# design.net
KiCad netlist of a schematic drawn in Altium Designer
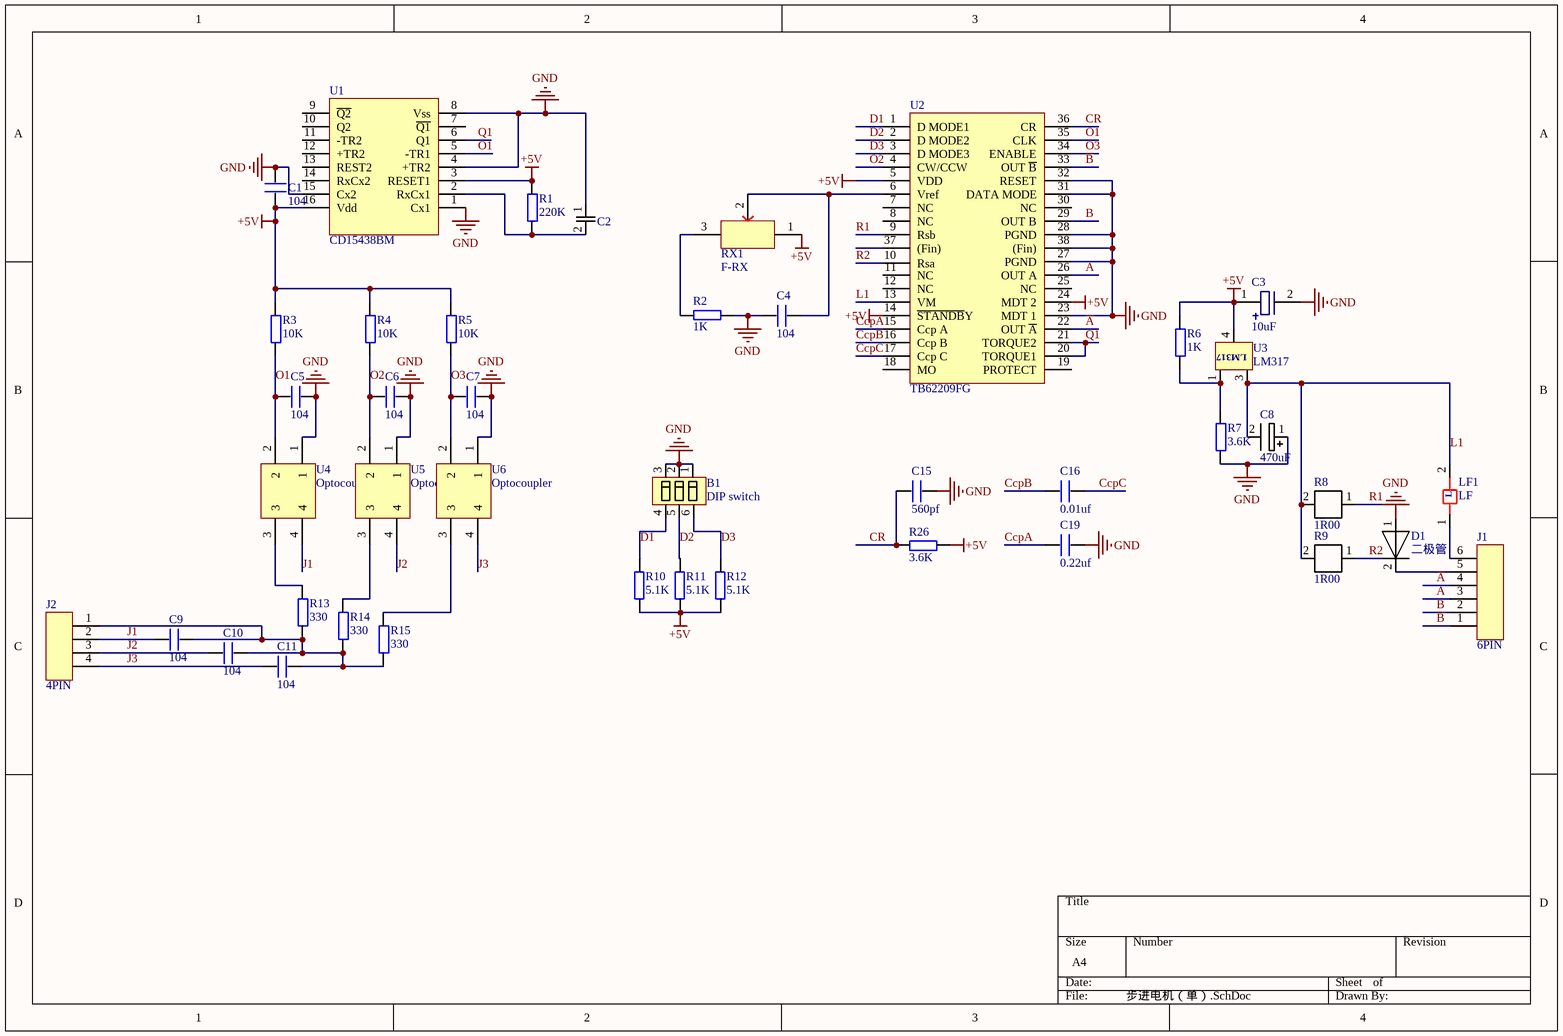
[diagram p0: 步进电机（单）.SchDoc]

(export (version "E")
  (design (tool "Eeschema 10.0.6"))
  (components
    (comp (ref "B1") (value "DIP switch") (libsource (lib "*") (part "拨码开关-3")))
    (comp (ref "C1") (value "104") (footprint "0603P") (libsource (lib "底板封装库") (part "C")))
    (comp (ref "C2") (value "SOP-CAP") (footprint "0805") (libsource (lib "mylib") (part "SOP-CAP")))
    (comp (ref "C3") (value "10uF") (footprint "CAP") (libsource (lib "*") (part "cap10uF")))
    (comp (ref "C4") (value "104") (footprint "0603P") (libsource (lib "底板封装库") (part "C")))
    (comp (ref "C5") (value "104") (footprint "0603P") (libsource (lib "底板封装库") (part "C")))
    (comp (ref "C6") (value "104") (footprint "0603P") (libsource (lib "底板封装库") (part "C")))
    (comp (ref "C7") (value "104") (footprint "0603P") (libsource (lib "底板封装库") (part "C")))
    (comp (ref "C8") (value "470uF") (footprint "470uF CAP") (libsource (lib "*") (part "470uF")))
    (comp (ref "C9") (value "104") (footprint "0603P") (libsource (lib "底板封装库") (part "C")))
    (comp (ref "C10") (value "104") (footprint "0603P") (libsource (lib "底板封装库") (part "C")))
    (comp (ref "C11") (value "104") (footprint "0603P") (libsource (lib "底板封装库") (part "C")))
    (comp (ref "C15") (value "560pf") (footprint "0603P") (libsource (lib "底板封装库") (part "C")))
    (comp (ref "C16") (value "0.01uf") (footprint "0603P") (libsource (lib "底板封装库") (part "C")))
    (comp (ref "C19") (value "0.22uf") (footprint "0603P") (libsource (lib "底板封装库") (part "C")))
    (comp (ref "D1") (value "二极管") (libsource (lib "*") (part "二极管")))
    (comp (ref "J1") (value "6PIN") (footprint "6PIN") (libsource (lib "*") (part "6PIN")))
    (comp (ref "J2") (value "4PIN") (footprint "4PIN") (libsource (lib "*") (part "4PIN")))
    (comp (ref "LF1") (value "LF") (footprint "LF") (libsource (lib "*") (part "LF")))
    (comp (ref "R1")
      (value "220K")
      (footprint "0603P")
      (fields (field (name "Comment") "22R"))
      (libsource (lib "底板封装库") (part "R"))
    )
    (comp (ref "R2")
      (value "1K")
      (footprint "0603P")
      (fields (field (name "Comment") "22R"))
      (libsource (lib "底板封装库") (part "R"))
    )
    (comp (ref "R3")
      (value "10K")
      (footprint "0603P")
      (fields (field (name "Comment") "22R"))
      (libsource (lib "底板封装库") (part "R"))
    )
    (comp (ref "R4")
      (value "10K")
      (footprint "0603P")
      (fields (field (name "Comment") "22R"))
      (libsource (lib "底板封装库") (part "R"))
    )
    (comp (ref "R5")
      (value "10K")
      (footprint "0603P")
      (fields (field (name "Comment") "22R"))
      (libsource (lib "底板封装库") (part "R"))
    )
    (comp (ref "R6")
      (value "1K")
      (footprint "0603P")
      (fields (field (name "Comment") "22R"))
      (libsource (lib "底板封装库") (part "R"))
    )
    (comp (ref "R7")
      (value "3.6K")
      (footprint "0603P")
      (fields (field (name "Comment") "22R"))
      (libsource (lib "底板封装库") (part "R"))
    )
    (comp (ref "R8") (value "1R00") (footprint "1R00") (libsource (lib "mylib") (part "1R00")))
    (comp (ref "R9") (value "1R00") (footprint "1R00") (libsource (lib "mylib") (part "1R00")))
    (comp (ref "R10")
      (value "5.1K")
      (footprint "0603P")
      (fields (field (name "Comment") "22R"))
      (libsource (lib "底板封装库") (part "R"))
    )
    (comp (ref "R11")
      (value "5.1K")
      (footprint "0603P")
      (fields (field (name "Comment") "22R"))
      (libsource (lib "底板封装库") (part "R"))
    )
    (comp (ref "R12")
      (value "5.1K")
      (footprint "0603P")
      (fields (field (name "Comment") "22R"))
      (libsource (lib "底板封装库") (part "R"))
    )
    (comp (ref "R13")
      (value "330")
      (footprint "0603P")
      (fields (field (name "Comment") "22R"))
      (libsource (lib "底板封装库") (part "R"))
    )
    (comp (ref "R14")
      (value "330")
      (footprint "0603P")
      (fields (field (name "Comment") "22R"))
      (libsource (lib "底板封装库") (part "R"))
    )
    (comp (ref "R15")
      (value "330")
      (footprint "0603P")
      (fields (field (name "Comment") "22R"))
      (libsource (lib "底板封装库") (part "R"))
    )
    (comp (ref "R26")
      (value "3.6K")
      (footprint "0603P")
      (fields (field (name "Comment") "22R"))
      (libsource (lib "底板封装库") (part "R"))
    )
    (comp (ref "RX1") (value "F-RX") (footprint "F-RX") (libsource (lib "*") (part "F-RX")))
    (comp (ref "U1") (value "CD15438BM") (footprint "CD14538BM") (libsource (lib "mylib") (part "CD15438BM")))
    (comp (ref "U2") (value "TB62209FG") (footprint "TB62209FG") (libsource (lib "*") (part "TB62209FG")))
    (comp (ref "U3") (value "LM317") (footprint "LM317-SOP") (libsource (lib "*") (part "LM317")))
    (comp (ref "U4") (value "Optocoupler") (libsource (lib "*") (part "光耦")))
    (comp (ref "U5") (value "Optocoupler") (libsource (lib "*") (part "光耦")))
    (comp (ref "U6") (value "Optocoupler") (libsource (lib "*") (part "光耦")))
  )
  (nets
    (net (code "1") (name "+5V") (class "Default")
      (node (ref "C1") (pin "1") (pintype "passive"))
      (node (ref "C3") (pin "1") (pintype "passive"))
      (node (ref "R1") (pin "2") (pintype "passive"))
      (node (ref "R10") (pin "2") (pintype "passive"))
      (node (ref "R11") (pin "2") (pintype "passive"))
      (node (ref "R12") (pin "2") (pintype "passive"))
      (node (ref "R26") (pin "2") (pintype "passive"))
      (node (ref "R3") (pin "2") (pintype "passive"))
      (node (ref "R4") (pin "2") (pintype "passive"))
      (node (ref "R5") (pin "2") (pintype "passive"))
      (node (ref "R6") (pin "2") (pintype "passive"))
      (node (ref "RX1") (pin "1") (pinfunction "1_1") (pintype "passive"))
      (node (ref "U1") (pin "16") (pinfunction "Vdd_16") (pintype "passive"))
      (node (ref "U1") (pin "3") (pinfunction "RESET1_3") (pintype "passive"))
      (node (ref "U2") (pin "14") (pinfunction "~{STANDB}Y_14") (pintype "passive"))
      (node (ref "U2") (pin "24") (pinfunction "MDT_2_24") (pintype "passive"))
      (node (ref "U2") (pin "5") (pinfunction "VDD_5") (pintype "passive"))
      (node (ref "U3") (pin "4") (pinfunction "4_4") (pintype "passive"))
    )
    (net (code "2") (name "/A") (class "Default")
      (node (ref "J1") (pin "3") (pinfunction "3_3") (pintype "passive"))
      (node (ref "U2") (pin "26") (pinfunction "OUT_A_26") (pintype "passive"))
    )
    (net (code "3") (name "/B") (class "Default")
      (node (ref "J1") (pin "2") (pinfunction "2_2") (pintype "passive"))
      (node (ref "U2") (pin "29") (pinfunction "OUT_B_29") (pintype "passive"))
    )
    (net (code "4") (name "/CR") (class "Default")
      (node (ref "C15") (pin "1") (pintype "passive"))
      (node (ref "R26") (pin "1") (pintype "passive"))
      (node (ref "U2") (pin "36") (pinfunction "CR_36") (pintype "passive"))
    )
    (net (code "5") (name "/CcpA") (class "Default")
      (node (ref "C19") (pin "1") (pintype "passive"))
      (node (ref "U2") (pin "15") (pinfunction "Ccp_A_15") (pintype "passive"))
    )
    (net (code "6") (name "/CcpB") (class "Default")
      (node (ref "C16") (pin "1") (pintype "passive"))
      (node (ref "U2") (pin "16") (pinfunction "Ccp_B_16") (pintype "passive"))
    )
    (net (code "7") (name "/CcpC") (class "Default")
      (node (ref "C16") (pin "2") (pintype "passive"))
      (node (ref "U2") (pin "17") (pinfunction "Ccp_C_17") (pintype "passive"))
    )
    (net (code "8") (name "/D1") (class "Default")
      (node (ref "B1") (pin "4") (pinfunction "4_4") (pintype "passive"))
      (node (ref "R10") (pin "1") (pintype "passive"))
      (node (ref "U2") (pin "1") (pinfunction "D_MODE1_1") (pintype "passive"))
    )
    (net (code "9") (name "/D2") (class "Default")
      (node (ref "B1") (pin "5") (pinfunction "5_5") (pintype "passive"))
      (node (ref "R11") (pin "1") (pintype "passive"))
      (node (ref "U2") (pin "2") (pinfunction "D_MODE2_2") (pintype "passive"))
    )
    (net (code "10") (name "/D3") (class "Default")
      (node (ref "B1") (pin "6") (pinfunction "6_6") (pintype "passive"))
      (node (ref "R12") (pin "1") (pintype "passive"))
      (node (ref "U2") (pin "3") (pinfunction "D_MODE3_3") (pintype "passive"))
    )
    (net (code "11") (name "/J1") (class "Default")
      (node (ref "C9") (pin "1") (pintype "passive"))
      (node (ref "J2") (pin "2") (pinfunction "2_2") (pintype "passive"))
      (node (ref "U4") (pin "4") (pinfunction "4_4") (pintype "passive"))
    )
    (net (code "12") (name "/J2") (class "Default")
      (node (ref "C10") (pin "1") (pintype "passive"))
      (node (ref "J2") (pin "3") (pinfunction "3_3") (pintype "passive"))
      (node (ref "U5") (pin "4") (pinfunction "4_4") (pintype "passive"))
    )
    (net (code "13") (name "/J3") (class "Default")
      (node (ref "C11") (pin "1") (pintype "passive"))
      (node (ref "J2") (pin "4") (pinfunction "4_4") (pintype "passive"))
      (node (ref "U6") (pin "4") (pinfunction "4_4") (pintype "passive"))
    )
    (net (code "14") (name "/L1") (class "Default")
      (node (ref "C8") (pin "2") (pinfunction "2_2") (pintype "passive"))
      (node (ref "LF1") (pin "2") (pinfunction "2_2") (pintype "passive"))
      (node (ref "R8") (pin "2") (pinfunction "2_2") (pintype "passive"))
      (node (ref "R9") (pin "2") (pinfunction "2_2") (pintype "passive"))
      (node (ref "U2") (pin "13") (pinfunction "VM_13") (pintype "passive"))
      (node (ref "U3") (pin "3") (pinfunction "3_3") (pintype "passive"))
    )
    (net (code "15") (name "/O1") (class "Default")
      (node (ref "C5") (pin "1") (pintype "passive"))
      (node (ref "R3") (pin "1") (pintype "passive"))
      (node (ref "U1") (pin "5") (pinfunction "-TR1_5") (pintype "passive"))
      (node (ref "U2") (pin "35") (pinfunction "CLK_35") (pintype "passive"))
      (node (ref "U4") (pin "2") (pinfunction "2_2") (pintype "passive"))
    )
    (net (code "16") (name "/O2") (class "Default")
      (node (ref "C6") (pin "1") (pintype "passive"))
      (node (ref "R4") (pin "1") (pintype "passive"))
      (node (ref "U2") (pin "4") (pinfunction "CW/CCW_4") (pintype "passive"))
      (node (ref "U5") (pin "2") (pinfunction "2_2") (pintype "passive"))
    )
    (net (code "17") (name "/O3") (class "Default")
      (node (ref "C7") (pin "1") (pintype "passive"))
      (node (ref "R5") (pin "1") (pintype "passive"))
      (node (ref "U2") (pin "34") (pinfunction "ENABLE_34") (pintype "passive"))
      (node (ref "U6") (pin "2") (pinfunction "2_2") (pintype "passive"))
    )
    (net (code "18") (name "/Q1") (class "Default")
      (node (ref "U1") (pin "6") (pinfunction "Q1_6") (pintype "passive"))
      (node (ref "U2") (pin "20") (pinfunction "TORQUE1_20") (pintype "passive"))
      (node (ref "U2") (pin "21") (pinfunction "TORQUE2_21") (pintype "passive"))
    )
    (net (code "19") (name "/R1") (class "Default")
      (node (ref "R8") (pin "1") (pinfunction "1_1") (pintype "passive"))
      (node (ref "U2") (pin "9") (pinfunction "Rsb_9") (pintype "passive"))
    )
    (net (code "20") (name "/R2") (class "Default")
      (node (ref "R9") (pin "1") (pinfunction "1_1") (pintype "passive"))
      (node (ref "U2") (pin "10") (pinfunction "Rsa_10") (pintype "passive"))
    )
    (net (code "21") (name "/~{A}") (class "Default")
      (node (ref "J1") (pin "4") (pinfunction "4_4") (pintype "passive"))
      (node (ref "U2") (pin "22") (pinfunction "OUT_~{A}_22") (pintype "passive"))
    )
    (net (code "22") (name "/~{B}") (class "Default")
      (node (ref "J1") (pin "1") (pinfunction "1_1") (pintype "passive"))
      (node (ref "U2") (pin "33") (pinfunction "OUT_~{B}_33") (pintype "passive"))
    )
    (net (code "23") (name "GND") (class "Default")
      (node (ref "B1") (pin "1") (pinfunction "1_1") (pintype "passive"))
      (node (ref "B1") (pin "2") (pinfunction "2_2") (pintype "passive"))
      (node (ref "B1") (pin "3") (pinfunction "3_3") (pintype "passive"))
      (node (ref "C1") (pin "2") (pintype "passive"))
      (node (ref "C15") (pin "2") (pintype "passive"))
      (node (ref "C19") (pin "2") (pintype "passive"))
      (node (ref "C2") (pin "1") (pinfunction "1_1") (pintype "passive"))
      (node (ref "C3") (pin "2") (pintype "passive"))
      (node (ref "C4") (pin "1") (pintype "passive"))
      (node (ref "C5") (pin "2") (pintype "passive"))
      (node (ref "C6") (pin "2") (pintype "passive"))
      (node (ref "C7") (pin "2") (pintype "passive"))
      (node (ref "C8") (pin "1") (pinfunction "1_1") (pintype "passive"))
      (node (ref "D1") (pin "1") (pinfunction "1_1") (pintype "passive"))
      (node (ref "R2") (pin "1") (pintype "passive"))
      (node (ref "R7") (pin "1") (pintype "passive"))
      (node (ref "U1") (pin "1") (pinfunction "Cx1_1") (pintype "passive"))
      (node (ref "U1") (pin "15") (pinfunction "Cx2_15") (pintype "passive"))
      (node (ref "U1") (pin "4") (pinfunction "+TR2_4") (pintype "passive"))
      (node (ref "U1") (pin "8") (pinfunction "Vss_8") (pintype "passive"))
      (node (ref "U2") (pin "23") (pinfunction "MDT_1_23") (pintype "passive"))
      (node (ref "U2") (pin "27") (pinfunction "PGND_27") (pintype "passive"))
      (node (ref "U2") (pin "28") (pinfunction "PGND_28") (pintype "passive"))
      (node (ref "U2") (pin "31") (pinfunction "DATA_MODE_31") (pintype "passive"))
      (node (ref "U2") (pin "32") (pinfunction "RESET_32") (pintype "passive"))
      (node (ref "U2") (pin "38") (pinfunction "(Fin)_38") (pintype "passive"))
      (node (ref "U4") (pin "1") (pinfunction "1_1") (pintype "passive"))
      (node (ref "U5") (pin "1") (pinfunction "1_1") (pintype "passive"))
      (node (ref "U6") (pin "1") (pinfunction "1_1") (pintype "passive"))
    )
    (net (code "24") (name "Net-(C10-Pad2)") (class "Default")
      (node (ref "C10") (pin "2") (pintype "passive"))
      (node (ref "C11") (pin "2") (pintype "passive"))
      (node (ref "C9") (pin "2") (pintype "passive"))
      (node (ref "J2") (pin "1") (pinfunction "1_1") (pintype "passive"))
      (node (ref "R13") (pin "1") (pintype "passive"))
      (node (ref "R14") (pin "1") (pintype "passive"))
      (node (ref "R15") (pin "1") (pintype "passive"))
    )
    (net (code "25") (name "Net-(D1-Pad2)") (class "Default")
      (node (ref "D1") (pin "2") (pinfunction "2_2") (pintype "passive"))
      (node (ref "J1") (pin "5") (pinfunction "5_5") (pintype "passive"))
    )
    (net (code "26") (name "Net-(J1-Pad6)") (class "Default")
      (node (ref "J1") (pin "6") (pinfunction "6_6") (pintype "passive"))
      (node (ref "LF1") (pin "1") (pinfunction "1_1") (pintype "passive"))
    )
    (net (code "27") (name "Net-(R2-Pad2)") (class "Default")
      (node (ref "R2") (pin "2") (pintype "passive"))
      (node (ref "RX1") (pin "3") (pinfunction "3_3") (pintype "passive"))
    )
    (net (code "28") (name "Net-(R6-Pad1)") (class "Default")
      (node (ref "R6") (pin "1") (pintype "passive"))
      (node (ref "R7") (pin "2") (pintype "passive"))
      (node (ref "U3") (pin "1") (pinfunction "1_1") (pintype "passive"))
    )
    (net (code "29") (name "Net-(R13-Pad2)") (class "Default")
      (node (ref "R13") (pin "2") (pintype "passive"))
      (node (ref "U4") (pin "3") (pinfunction "3_3") (pintype "passive"))
    )
    (net (code "30") (name "Net-(R14-Pad2)") (class "Default")
      (node (ref "R14") (pin "2") (pintype "passive"))
      (node (ref "U5") (pin "3") (pinfunction "3_3") (pintype "passive"))
    )
    (net (code "31") (name "Net-(R15-Pad2)") (class "Default")
      (node (ref "R15") (pin "2") (pintype "passive"))
      (node (ref "U6") (pin "3") (pinfunction "3_3") (pintype "passive"))
    )
    (net (code "32") (name "Net-(U1-RxCx1)") (class "Default")
      (node (ref "C2") (pin "2") (pinfunction "2_2") (pintype "passive"))
      (node (ref "R1") (pin "1") (pintype "passive"))
      (node (ref "U1") (pin "2") (pinfunction "RxCx1_2") (pintype "passive"))
    )
    (net (code "33") (name "Net-(U2-Vref)") (class "Default")
      (node (ref "C4") (pin "2") (pintype "passive"))
      (node (ref "RX1") (pin "2") (pinfunction "2_2") (pintype "passive"))
      (node (ref "U2") (pin "6") (pinfunction "Vref_6") (pintype "passive"))
    )
    (net (code "34") (name "unconnected-(U1-+TR2-Pad12)") (class "Default")
      (node (ref "U1") (pin "12") (pinfunction "+TR2_12") (pintype "passive"))
    )
    (net (code "35") (name "unconnected-(U1--TR2-Pad11)") (class "Default")
      (node (ref "U1") (pin "11") (pinfunction "-TR2_11") (pintype "passive"))
    )
    (net (code "36") (name "unconnected-(U1-Q2-Pad10)") (class "Default")
      (node (ref "U1") (pin "10") (pinfunction "Q2_10") (pintype "passive"))
    )
    (net (code "37") (name "unconnected-(U1-REST2-Pad13)") (class "Default")
      (node (ref "U1") (pin "13") (pinfunction "REST2_13") (pintype "passive"))
    )
    (net (code "38") (name "unconnected-(U1-RxCx2-Pad14)") (class "Default")
      (node (ref "U1") (pin "14") (pinfunction "RxCx2_14") (pintype "passive"))
    )
    (net (code "39") (name "unconnected-(U1-~{Q1}-Pad7)") (class "Default")
      (node (ref "U1") (pin "7") (pinfunction "~{Q1}_7") (pintype "passive"))
    )
    (net (code "40") (name "unconnected-(U1-~{Q2}-Pad9)") (class "Default")
      (node (ref "U1") (pin "9") (pinfunction "~{Q2}_9") (pintype "passive"))
    )
    (net (code "41") (name "unconnected-(U2-(Fin)-Pad37)") (class "Default")
      (node (ref "U2") (pin "37") (pinfunction "(Fin)_37") (pintype "passive"))
    )
    (net (code "42") (name "unconnected-(U2-MO-Pad18)") (class "Default")
      (node (ref "U2") (pin "18") (pinfunction "MO_18") (pintype "passive"))
    )
    (net (code "43") (name "unconnected-(U2-NC-Pad7)") (class "Default")
      (node (ref "U2") (pin "7") (pinfunction "NC_7") (pintype "passive"))
    )
    (net (code "44") (name "unconnected-(U2-NC-Pad8)") (class "Default")
      (node (ref "U2") (pin "8") (pinfunction "NC_8") (pintype "passive"))
    )
    (net (code "45") (name "unconnected-(U2-NC-Pad11)") (class "Default")
      (node (ref "U2") (pin "11") (pinfunction "NC_11") (pintype "passive"))
    )
    (net (code "46") (name "unconnected-(U2-NC-Pad12)") (class "Default")
      (node (ref "U2") (pin "12") (pinfunction "NC_12") (pintype "passive"))
    )
    (net (code "47") (name "unconnected-(U2-NC-Pad25)") (class "Default")
      (node (ref "U2") (pin "25") (pinfunction "NC_25") (pintype "passive"))
    )
    (net (code "48") (name "unconnected-(U2-NC-Pad30)") (class "Default")
      (node (ref "U2") (pin "30") (pinfunction "NC_30") (pintype "passive"))
    )
    (net (code "49") (name "unconnected-(U2-PROTECT-Pad19)") (class "Default")
      (node (ref "U2") (pin "19") (pinfunction "PROTECT_19") (pintype "passive"))
    )
  )
)
